# Connectors.net
KiCad netlist of a schematic drawn in Altium Designer
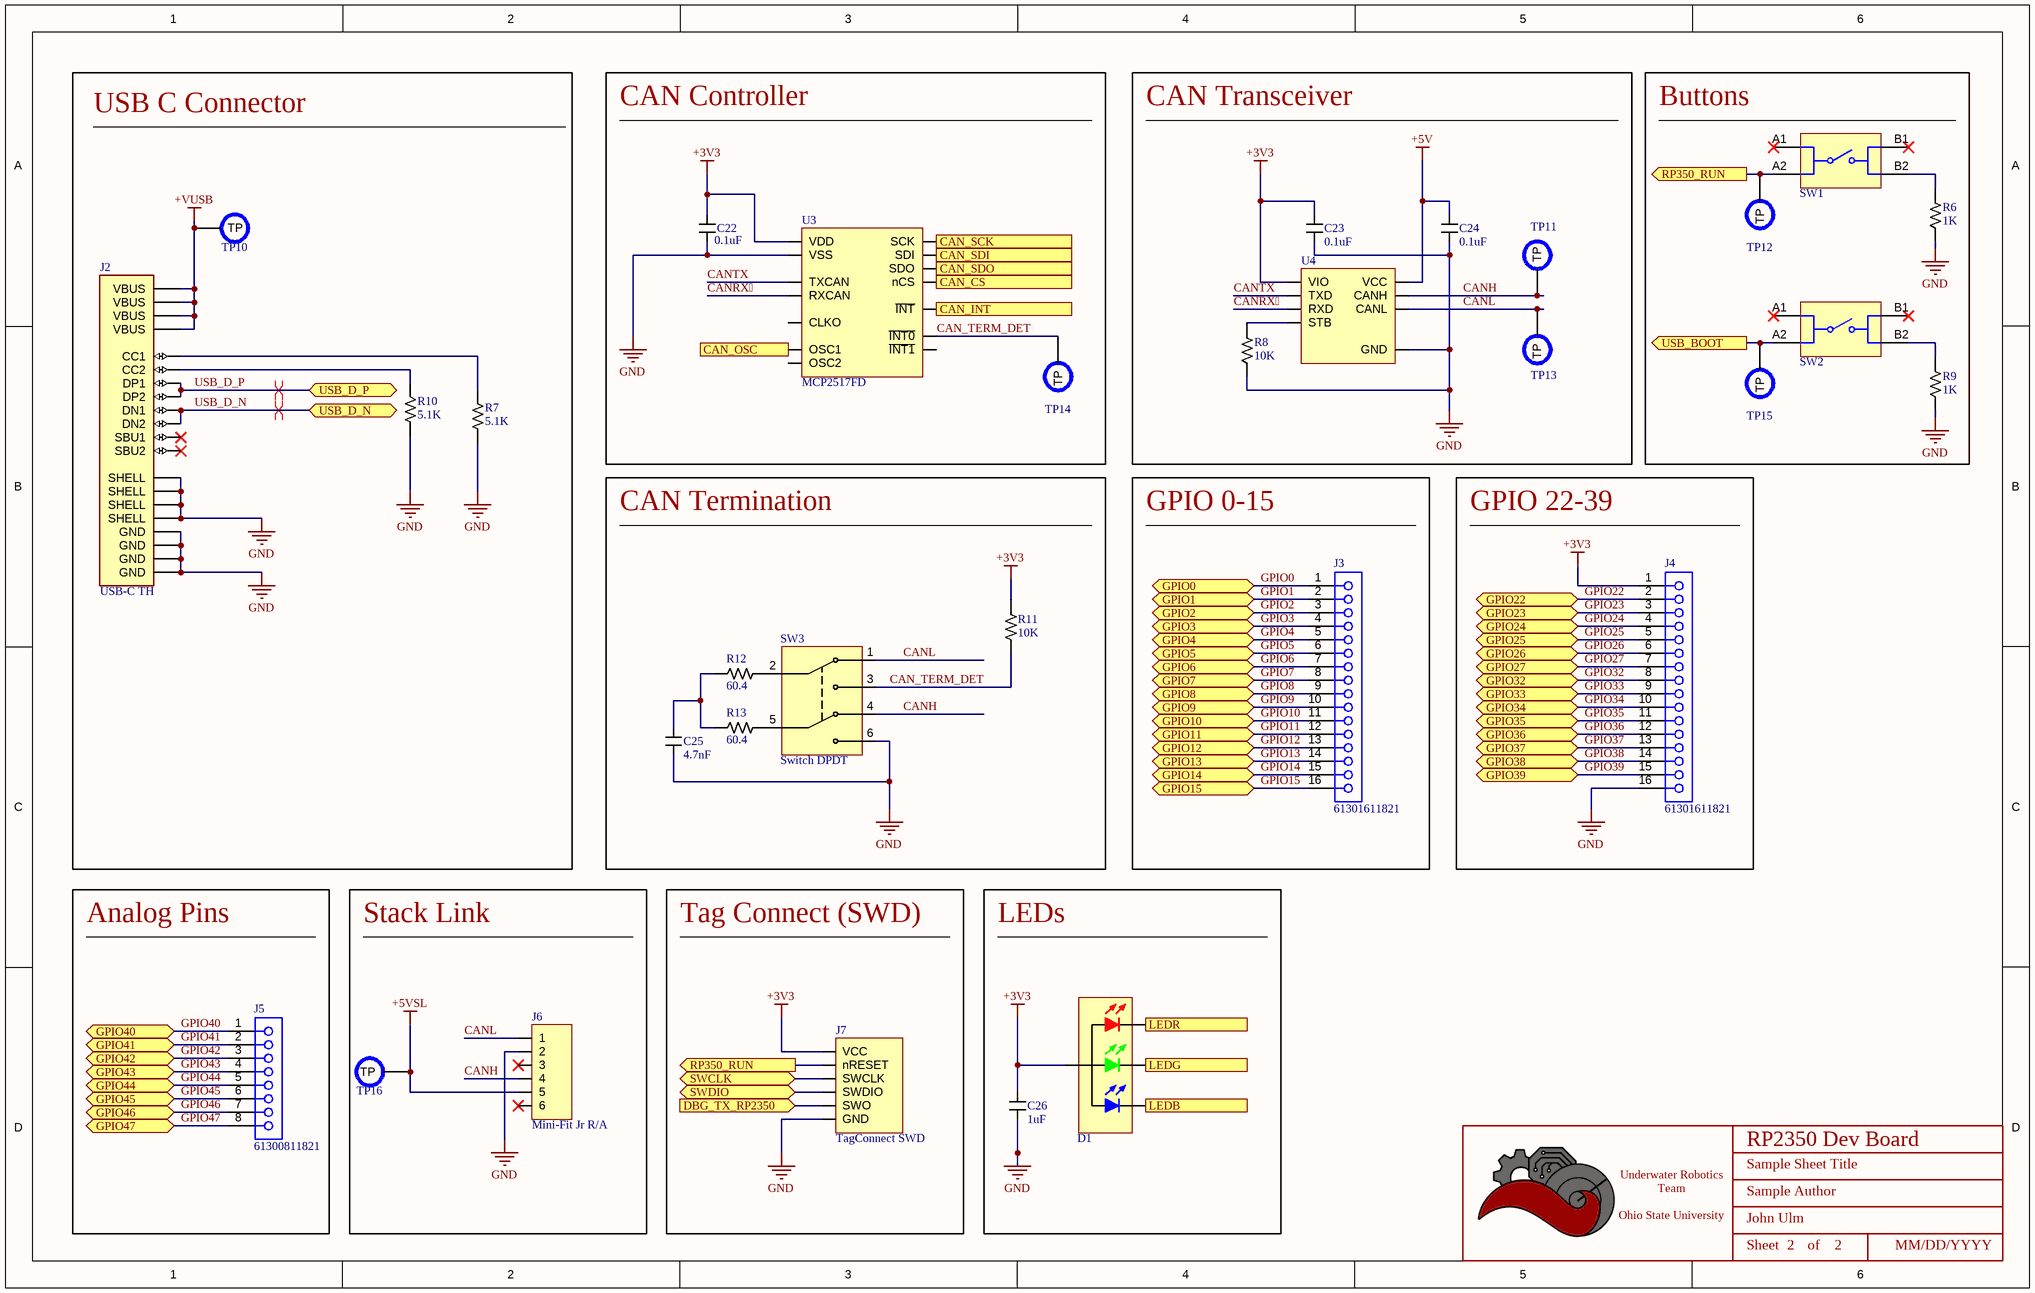
[diagram p0: Connectors.SchDoc]

(export (version "E")
  (design (tool "Eeschema 10.0.6"))
  (components
    (comp (ref "C22")
      (value "0.1uF")
      (footprint "CAPACITOR_0603")
      (description "Cap 100nF 25V +/-10%\r\nCeramic 0603")
      (fields
        (field (name "TOLERANCE") "+/- 10%")
        (field (name "VOLTAGE") "6.3V")
        (field (name "MADE BY") "Flip B")
      )
      (libsource (lib "Capacitors") (part "CAPACITOR_0.1uF_0603_25V"))
    )
    (comp (ref "C23")
      (value "0.1uF")
      (footprint "CAPACITOR_0603")
      (description "Cap 100nF 25V +/-10%\r\nCeramic 0603")
      (fields
        (field (name "TOLERANCE") "+/- 10%")
        (field (name "VOLTAGE") "6.3V")
        (field (name "MADE BY") "Flip B")
      )
      (libsource (lib "Capacitors") (part "CAPACITOR_0.1uF_0603_25V"))
    )
    (comp (ref "C24")
      (value "0.1uF")
      (footprint "CAPACITOR_0603")
      (description "Cap 100nF 25V +/-10%\r\nCeramic 0603")
      (fields
        (field (name "TOLERANCE") "+/- 10%")
        (field (name "VOLTAGE") "6.3V")
        (field (name "MADE BY") "Flip B")
      )
      (libsource (lib "Capacitors") (part "CAPACITOR_0.1uF_0603_25V"))
    )
    (comp (ref "C25")
      (value "4.7nF")
      (footprint "CAPACITOR_0402")
      (description "4700 pF +/-10% 25V Ceramic Capacitor X7R 0402")
      (fields
        (field (name "TOLERANCE") "+/- 10%")
        (field (name "VOLTAGE") "25V")
        (field (name "MADE BY") "Robert Pafford")
      )
      (libsource (lib "Capacitors") (part "CAPACITOR_0.0047uF_0402"))
    )
    (comp (ref "C26")
      (value "1uF")
      (footprint "CAPACITOR_0603")
      (description "Cap 1uF 16V +/-10%\r\nCeramic 0603")
      (fields
        (field (name "TOLERANCE") "+/- 10%")
        (field (name "VOLTAGE") "16V")
        (field (name "MADE BY") "Flip B")
      )
      (libsource (lib "Capacitors") (part "CAPACITOR_1uF_0603"))
    )
    (comp (ref "D1")
      (value "EAST1616RGBB4")
      (footprint "LED_0606_4SMD")
      (description "LED RGB CLEAR 4SMD")
      (fields (field (name "MADE BY") "Robert Pafford"))
      (libsource (lib "Diodes") (part "LED_RGB_4SMD"))
    )
    (comp (ref "J2")
      (value "USB-C TH")
      (footprint "USB-C TH")
      (description "USB-C (USB TYPE-C) USB 2.0 Receptacle Connector 24 (16+8 Dummy) Position Through Hole, Right Angle")
      (fields (field (name "CREATED BY") "John Ulm"))
      (libsource (lib "Connectors") (part "CONN_USBC_USB4085-GF-A"))
    )
    (comp (ref "J3")
      (value "61301611821")
      (footprint "61301611821")
      (libsource (lib "Altium Content Vault") (part "Header_Female_1R_16P"))
    )
    (comp (ref "J4")
      (value "61301611821")
      (footprint "61301611821")
      (libsource (lib "Altium Content Vault") (part "Header_Female_1R_16P"))
    )
    (comp (ref "J5")
      (value "61300811821")
      (footprint "61300811821")
      (libsource (lib "Altium Content Vault") (part "Header_Female_1R_08P"))
    )
    (comp (ref "J6")
      (value "Mini-Fit Jr R/A")
      (footprint "CONN_MOLEX_MINIFIT JR_6 POS_R/A")
      (description "Molex Minifit Jr. 5569 \r\n6 Pos R/A Natural")
      (fields (field (name "MANUFACTURER") "Molex") (field (name "CREATED BY") "Flip B"))
      (libsource (lib "Connectors") (part "CONN_MOLEX_MINIFIT JR_6POS_R/A"))
    )
    (comp (ref "J7")
      (value "TagConnect SWD")
      (footprint "TC2030-MCP")
      (description "TagConnect TC2030 ARM SWD 6-pin")
      (libsource (lib "Connectors") (part "TC2030_SWD"))
    )
    (comp (ref "R6")
      (value "1k Ohm 5% 1/8W")
      (footprint "RESISTOR_0603")
      (description "RES 1k OHM 5% 1/8W 0603")
      (fields
        (field (name "TOLERANCE") "+/- 5%")
        (field (name "VALUE  (OHMS)") "1K")
        (field (name "MADE BY") "Robert Pafford")
      )
      (libsource (lib "Resistors") (part "RESISTOR_1K_0603"))
    )
    (comp (ref "R7")
      (value "5.1k Ohm 1% 1/8W")
      (footprint "RESISTOR_0805")
      (description "RES 5.1k OHM 1% 1/8W 0805")
      (fields
        (field (name "TOLERANCE") "+/- 5%")
        (field (name "VALUE  (OHMS)") "5.1K")
        (field (name "MADE BY") "Dylan Trainor")
      )
      (libsource (lib "Resistors") (part "RESISTOR_5.1K_0805"))
    )
    (comp (ref "R8")
      (value "10k Ohm 1% 1/16W")
      (footprint "RESISTOR_0402")
      (description "RES 10k OHM 1% 1/16W 0402")
      (fields
        (field (name "TOLERANCE") "+/- 1%")
        (field (name "VALUE  (OHMS)") "10K")
        (field (name "MADE BY") "Robert Pafford")
      )
      (libsource (lib "Resistors") (part "RESISTOR_10K_0402"))
    )
    (comp (ref "R9")
      (value "1k Ohm 5% 1/8W")
      (footprint "RESISTOR_0603")
      (description "RES 1k OHM 5% 1/8W 0603")
      (fields
        (field (name "TOLERANCE") "+/- 5%")
        (field (name "VALUE  (OHMS)") "1K")
        (field (name "MADE BY") "Robert Pafford")
      )
      (libsource (lib "Resistors") (part "RESISTOR_1K_0603"))
    )
    (comp (ref "R10")
      (value "5.1k Ohm 1% 1/8W")
      (footprint "RESISTOR_0805")
      (description "RES 5.1k OHM 1% 1/8W 0805")
      (fields
        (field (name "TOLERANCE") "+/- 5%")
        (field (name "VALUE  (OHMS)") "5.1K")
        (field (name "MADE BY") "Dylan Trainor")
      )
      (libsource (lib "Resistors") (part "RESISTOR_5.1K_0805"))
    )
    (comp (ref "R11")
      (value "10k Ohm 1% 1/16W")
      (footprint "RESISTOR_0402")
      (description "RES 10k OHM 1% 1/16W 0402")
      (fields
        (field (name "TOLERANCE") "+/- 1%")
        (field (name "VALUE  (OHMS)") "10K")
        (field (name "MADE BY") "Robert Pafford")
      )
      (libsource (lib "Resistors") (part "RESISTOR_10K_0402"))
    )
    (comp (ref "R12")
      (value "60.4 Ohm 1% 1/16W")
      (footprint "RESISTOR_0402")
      (description "RES 60.4 OHM 1% 1/16W 0402")
      (fields
        (field (name "TOLERANCE") "+/- 1%")
        (field (name "VALUE  (OHMS)") "60.4")
        (field (name "MADE BY") "Robert Pafford")
      )
      (libsource (lib "Resistors") (part "RESISTOR_60.4_0402"))
    )
    (comp (ref "R13")
      (value "60.4 Ohm 1% 1/16W")
      (footprint "RESISTOR_0402")
      (description "RES 60.4 OHM 1% 1/16W 0402")
      (fields
        (field (name "TOLERANCE") "+/- 1%")
        (field (name "VALUE  (OHMS)") "60.4")
        (field (name "MADE BY") "Robert Pafford")
      )
      (libsource (lib "Resistors") (part "RESISTOR_60.4_0402"))
    )
    (comp (ref "SW1")
      (value "434123025826")
      (footprint "SMD_434123025826")
      (description "WS-TASV J-Bend SMT Tact Switch, SPST-NO, 16VDC, 50mA, 260g")
      (fields (field (name "MANUFACTURER") "Wurth Elektronik"))
      (libsource (lib "Switches") (part "Tactile Switch SMD"))
    )
    (comp (ref "SW2")
      (value "434123025826")
      (footprint "SMD_434123025826")
      (description "WS-TASV J-Bend SMT Tact Switch, SPST-NO, 16VDC, 50mA, 260g")
      (fields (field (name "MANUFACTURER") "Wurth Elektronik"))
      (libsource (lib "Switches") (part "Tactile Switch SMD"))
    )
    (comp (ref "SW3")
      (value "Switch DPDT")
      (footprint "CAS-220TA")
      (description "GOLD SWITCH FLUSH SLIDE DPDT 100MA 6V")
      (fields (field (name "MADE BY") "Robert Pafford"))
      (libsource (lib "Switches") (part "CAS-220TA_CAN_TERM"))
    )
    (comp (ref "TP10")
      (value "PCB Test Point")
      (footprint "TESTPOINT_1.2MM")
      (fields (field (name "MADE BY") "Robert Pafford"))
      (libsource (lib "Connectors") (part "TESTPOINT"))
    )
    (comp (ref "TP11")
      (value "PCB Test Point")
      (footprint "TESTPOINT_1.2MM")
      (fields (field (name "MADE BY") "Robert Pafford"))
      (libsource (lib "Connectors") (part "TESTPOINT"))
    )
    (comp (ref "TP12")
      (value "PCB Test Point")
      (footprint "TESTPOINT_1.2MM")
      (fields (field (name "MADE BY") "Robert Pafford"))
      (libsource (lib "Connectors") (part "TESTPOINT"))
    )
    (comp (ref "TP13")
      (value "PCB Test Point")
      (footprint "TESTPOINT_1.2MM")
      (fields (field (name "MADE BY") "Robert Pafford"))
      (libsource (lib "Connectors") (part "TESTPOINT"))
    )
    (comp (ref "TP14")
      (value "PCB Test Point")
      (footprint "TESTPOINT_1.2MM")
      (fields (field (name "MADE BY") "Robert Pafford"))
      (libsource (lib "Connectors") (part "TESTPOINT"))
    )
    (comp (ref "TP15")
      (value "PCB Test Point")
      (footprint "TESTPOINT_1.2MM")
      (fields (field (name "MADE BY") "Robert Pafford"))
      (libsource (lib "Connectors") (part "TESTPOINT"))
    )
    (comp (ref "TP16")
      (value "PCB Test Point")
      (footprint "TESTPOINT_1.2MM")
      (fields (field (name "MADE BY") "Robert Pafford"))
      (libsource (lib "Connectors") (part "TESTPOINT"))
    )
    (comp (ref "U3")
      (value "MCP2517FD")
      (footprint "SOIC-14")
      (description "CANbus Controller CAN 2.0 SPI Interface 14-SOIC")
      (fields (field (name "MADE BY") "Robert Pafford"))
      (libsource (lib "Integrated Circuits") (part "MCP2517FD"))
    )
    (comp (ref "U4")
      (value "CAN Transceiver")
      (footprint "SOIC-8")
      (description "CAN Interface IC High-Speed CAN Transceiver with Standby Mode")
      (fields (field (name "MADE BY") "Robert Pafford"))
      (libsource (lib "Integrated Circuits") (part "TJA1442AT"))
    )
  )
  (nets
    (net (code "1") (name "+3V3") (class "Default")
      (node (ref "C22") (pin "1") (pinfunction "1_1") (pintype "passive"))
      (node (ref "C23") (pin "1") (pinfunction "1_1") (pintype "passive"))
      (node (ref "C26") (pin "1") (pinfunction "1_1") (pintype "passive"))
      (node (ref "D1") (pin "4") (pinfunction "4_4") (pintype "passive"))
      (node (ref "J4") (pin "1") (pinfunction "1_1") (pintype "passive"))
      (node (ref "J7") (pin "2") (pinfunction "VCC_2") (pintype "passive"))
      (node (ref "R11") (pin "1") (pinfunction "1_1") (pintype "passive"))
      (node (ref "U3") (pin "14") (pinfunction "VDD_14") (pintype "passive"))
      (node (ref "U4") (pin "5") (pinfunction "VIO_5") (pintype "passive"))
    )
    (net (code "2") (name "+5V") (class "Default")
      (node (ref "C24") (pin "1") (pinfunction "1_1") (pintype "passive"))
      (node (ref "U4") (pin "3") (pinfunction "VCC_3") (pintype "passive"))
    )
    (net (code "3") (name "+5VSL") (class "Default")
      (node (ref "J6") (pin "5") (pinfunction "5_5") (pintype "passive"))
      (node (ref "TP16") (pin "TP") (pinfunction "TP_TP") (pintype "passive"))
    )
    (net (code "4") (name "+VUSB") (class "Default")
      (node (ref "J2") (pin "A4") (pinfunction "VBUS_A4") (pintype "power_in"))
      (node (ref "J2") (pin "A9") (pinfunction "VBUS_A9") (pintype "power_in"))
      (node (ref "J2") (pin "B4") (pinfunction "VBUS_B4") (pintype "power_in"))
      (node (ref "J2") (pin "B9") (pinfunction "VBUS_B9") (pintype "power_in"))
      (node (ref "TP10") (pin "TP") (pinfunction "TP_TP") (pintype "passive"))
    )
    (net (code "5") (name "/CANH") (class "Default")
      (node (ref "J6") (pin "4") (pinfunction "4_4") (pintype "passive"))
      (node (ref "SW3") (pin "4") (pintype "passive"))
      (node (ref "TP11") (pin "TP") (pinfunction "TP_TP") (pintype "passive"))
      (node (ref "U4") (pin "7") (pinfunction "CANH_7") (pintype "passive"))
    )
    (net (code "6") (name "/CANL") (class "Default")
      (node (ref "J6") (pin "1") (pinfunction "1_1") (pintype "passive"))
      (node (ref "SW3") (pin "1") (pintype "passive"))
      (node (ref "TP13") (pin "TP") (pinfunction "TP_TP") (pintype "passive"))
      (node (ref "U4") (pin "6") (pinfunction "CANL_6") (pintype "passive"))
    )
    (net (code "7") (name "/CANRX") (class "Default")
      (node (ref "U3") (pin "2") (pinfunction "RXCAN_2") (pintype "passive"))
      (node (ref "U4") (pin "4") (pinfunction "RXD_4") (pintype "passive"))
    )
    (net (code "8") (name "/CANTX") (class "Default")
      (node (ref "U3") (pin "1") (pinfunction "TXCAN_1") (pintype "passive"))
      (node (ref "U4") (pin "1") (pinfunction "TXD_1") (pintype "passive"))
    )
    (net (code "9") (name "/CAN_CS") (class "Default")
      (node (ref "U3") (pin "13") (pinfunction "nCS_13") (pintype "passive"))
    )
    (net (code "10") (name "/CAN_INT") (class "Default")
      (node (ref "U3") (pin "4") (pinfunction "~{INT}_4") (pintype "passive"))
    )
    (net (code "11") (name "/CAN_OSC") (class "Default")
      (node (ref "U3") (pin "6") (pinfunction "OSC1_6") (pintype "passive"))
    )
    (net (code "12") (name "/CAN_SCK") (class "Default")
      (node (ref "U3") (pin "10") (pinfunction "SCK_10") (pintype "passive"))
    )
    (net (code "13") (name "/CAN_SDI") (class "Default")
      (node (ref "U3") (pin "11") (pinfunction "SDI_11") (pintype "passive"))
    )
    (net (code "14") (name "/CAN_SDO") (class "Default")
      (node (ref "U3") (pin "12") (pinfunction "SDO_12") (pintype "passive"))
    )
    (net (code "15") (name "/CAN_TERM_DET") (class "Default")
      (node (ref "R11") (pin "2") (pinfunction "2_2") (pintype "passive"))
      (node (ref "SW3") (pin "3") (pintype "passive"))
      (node (ref "TP14") (pin "TP") (pinfunction "TP_TP") (pintype "passive"))
      (node (ref "U3") (pin "9") (pinfunction "~{INT0}_9") (pintype "passive"))
    )
    (net (code "16") (name "/DBG_TX_RP2350") (class "Default")
      (node (ref "J7") (pin "5") (pinfunction "SWO_5") (pintype "passive"))
    )
    (net (code "17") (name "/GPIO0") (class "Default")
      (node (ref "J3") (pin "1") (pinfunction "1_1") (pintype "passive"))
    )
    (net (code "18") (name "/GPIO1") (class "Default")
      (node (ref "J3") (pin "2") (pinfunction "2_2") (pintype "passive"))
    )
    (net (code "19") (name "/GPIO2") (class "Default")
      (node (ref "J3") (pin "3") (pinfunction "3_3") (pintype "passive"))
    )
    (net (code "20") (name "/GPIO3") (class "Default")
      (node (ref "J3") (pin "4") (pinfunction "4_4") (pintype "passive"))
    )
    (net (code "21") (name "/GPIO4") (class "Default")
      (node (ref "J3") (pin "5") (pinfunction "5_5") (pintype "passive"))
    )
    (net (code "22") (name "/GPIO5") (class "Default")
      (node (ref "J3") (pin "6") (pinfunction "6_6") (pintype "passive"))
    )
    (net (code "23") (name "/GPIO6") (class "Default")
      (node (ref "J3") (pin "7") (pinfunction "7_7") (pintype "passive"))
    )
    (net (code "24") (name "/GPIO7") (class "Default")
      (node (ref "J3") (pin "8") (pinfunction "8_8") (pintype "passive"))
    )
    (net (code "25") (name "/GPIO8") (class "Default")
      (node (ref "J3") (pin "9") (pinfunction "9_9") (pintype "passive"))
    )
    (net (code "26") (name "/GPIO9") (class "Default")
      (node (ref "J3") (pin "10") (pinfunction "10_10") (pintype "passive"))
    )
    (net (code "27") (name "/GPIO10") (class "Default")
      (node (ref "J3") (pin "11") (pinfunction "11_11") (pintype "passive"))
    )
    (net (code "28") (name "/GPIO11") (class "Default")
      (node (ref "J3") (pin "12") (pinfunction "12_12") (pintype "passive"))
    )
    (net (code "29") (name "/GPIO12") (class "Default")
      (node (ref "J3") (pin "13") (pinfunction "13_13") (pintype "passive"))
    )
    (net (code "30") (name "/GPIO13") (class "Default")
      (node (ref "J3") (pin "14") (pinfunction "14_14") (pintype "passive"))
    )
    (net (code "31") (name "/GPIO14") (class "Default")
      (node (ref "J3") (pin "15") (pinfunction "15_15") (pintype "passive"))
    )
    (net (code "32") (name "/GPIO15") (class "Default")
      (node (ref "J3") (pin "16") (pinfunction "16_16") (pintype "passive"))
    )
    (net (code "33") (name "/GPIO22") (class "Default")
      (node (ref "J4") (pin "2") (pinfunction "2_2") (pintype "passive"))
    )
    (net (code "34") (name "/GPIO23") (class "Default")
      (node (ref "J4") (pin "3") (pinfunction "3_3") (pintype "passive"))
    )
    (net (code "35") (name "/GPIO24") (class "Default")
      (node (ref "J4") (pin "4") (pinfunction "4_4") (pintype "passive"))
    )
    (net (code "36") (name "/GPIO25") (class "Default")
      (node (ref "J4") (pin "5") (pinfunction "5_5") (pintype "passive"))
    )
    (net (code "37") (name "/GPIO26") (class "Default")
      (node (ref "J4") (pin "6") (pinfunction "6_6") (pintype "passive"))
    )
    (net (code "38") (name "/GPIO27") (class "Default")
      (node (ref "J4") (pin "7") (pinfunction "7_7") (pintype "passive"))
    )
    (net (code "39") (name "/GPIO32") (class "Default")
      (node (ref "J4") (pin "8") (pinfunction "8_8") (pintype "passive"))
    )
    (net (code "40") (name "/GPIO33") (class "Default")
      (node (ref "J4") (pin "9") (pinfunction "9_9") (pintype "passive"))
    )
    (net (code "41") (name "/GPIO34") (class "Default")
      (node (ref "J4") (pin "10") (pinfunction "10_10") (pintype "passive"))
    )
    (net (code "42") (name "/GPIO35") (class "Default")
      (node (ref "J4") (pin "11") (pinfunction "11_11") (pintype "passive"))
    )
    (net (code "43") (name "/GPIO36") (class "Default")
      (node (ref "J4") (pin "12") (pinfunction "12_12") (pintype "passive"))
    )
    (net (code "44") (name "/GPIO37") (class "Default")
      (node (ref "J4") (pin "13") (pinfunction "13_13") (pintype "passive"))
    )
    (net (code "45") (name "/GPIO38") (class "Default")
      (node (ref "J4") (pin "14") (pinfunction "14_14") (pintype "passive"))
    )
    (net (code "46") (name "/GPIO39") (class "Default")
      (node (ref "J4") (pin "15") (pinfunction "15_15") (pintype "passive"))
    )
    (net (code "47") (name "/GPIO40") (class "Default")
      (node (ref "J5") (pin "1") (pinfunction "1_1") (pintype "passive"))
    )
    (net (code "48") (name "/GPIO41") (class "Default")
      (node (ref "J5") (pin "2") (pinfunction "2_2") (pintype "passive"))
    )
    (net (code "49") (name "/GPIO42") (class "Default")
      (node (ref "J5") (pin "3") (pinfunction "3_3") (pintype "passive"))
    )
    (net (code "50") (name "/GPIO43") (class "Default")
      (node (ref "J5") (pin "4") (pinfunction "4_4") (pintype "passive"))
    )
    (net (code "51") (name "/GPIO44") (class "Default")
      (node (ref "J5") (pin "5") (pinfunction "5_5") (pintype "passive"))
    )
    (net (code "52") (name "/GPIO45") (class "Default")
      (node (ref "J5") (pin "6") (pinfunction "6_6") (pintype "passive"))
    )
    (net (code "53") (name "/GPIO46") (class "Default")
      (node (ref "J5") (pin "7") (pinfunction "7_7") (pintype "passive"))
    )
    (net (code "54") (name "/GPIO47") (class "Default")
      (node (ref "J5") (pin "8") (pinfunction "8_8") (pintype "passive"))
    )
    (net (code "55") (name "/LEDB") (class "Default")
      (node (ref "D1") (pin "3") (pinfunction "32_3") (pintype "passive"))
    )
    (net (code "56") (name "/LEDG") (class "Default")
      (node (ref "D1") (pin "2") (pinfunction "2_2") (pintype "passive"))
    )
    (net (code "57") (name "/LEDR") (class "Default")
      (node (ref "D1") (pin "1") (pinfunction "1_1") (pintype "passive"))
    )
    (net (code "58") (name "/RP350_RUN") (class "Default")
      (node (ref "J7") (pin "4") (pinfunction "nRESET_4") (pintype "passive"))
      (node (ref "SW1") (pin "A2") (pinfunction "A2_A2") (pintype "passive"))
      (node (ref "TP12") (pin "TP") (pinfunction "TP_TP") (pintype "passive"))
    )
    (net (code "59") (name "/SWCLK") (class "Default")
      (node (ref "J7") (pin "3") (pinfunction "SWCLK_3") (pintype "passive"))
    )
    (net (code "60") (name "/SWDIO") (class "Default")
      (node (ref "J7") (pin "1") (pinfunction "SWDIO_1") (pintype "passive"))
    )
    (net (code "61") (name "/USB_BOOT") (class "Default")
      (node (ref "SW2") (pin "A2") (pinfunction "A2_A2") (pintype "passive"))
      (node (ref "TP15") (pin "TP") (pinfunction "TP_TP") (pintype "passive"))
    )
    (net (code "62") (name "/USB_D_N") (class "Default")
      (node (ref "J2") (pin "A7") (pinfunction "DN1_A7") (pintype "bidirectional"))
      (node (ref "J2") (pin "B7") (pinfunction "DN2_B7") (pintype "bidirectional"))
    )
    (net (code "63") (name "/USB_D_P") (class "Default")
      (node (ref "J2") (pin "A6") (pinfunction "DP1_A6") (pintype "bidirectional"))
      (node (ref "J2") (pin "B6") (pinfunction "DP2_B6") (pintype "bidirectional"))
    )
    (net (code "64") (name "GND") (class "Default")
      (node (ref "C22") (pin "2") (pinfunction "2_2") (pintype "passive"))
      (node (ref "C23") (pin "2") (pinfunction "2_2") (pintype "passive"))
      (node (ref "C24") (pin "2") (pinfunction "2_2") (pintype "passive"))
      (node (ref "C25") (pin "2") (pinfunction "2_2") (pintype "passive"))
      (node (ref "C26") (pin "2") (pinfunction "2_2") (pintype "passive"))
      (node (ref "J2") (pin "A1") (pinfunction "GND_A1") (pintype "power_in"))
      (node (ref "J2") (pin "A12") (pinfunction "GND_A12") (pintype "power_in"))
      (node (ref "J2") (pin "B1") (pinfunction "GND_B1") (pintype "power_in"))
      (node (ref "J2") (pin "B12") (pinfunction "GND_B12") (pintype "power_in"))
      (node (ref "J2") (pin "S1") (pinfunction "SHELL_S1") (pintype "passive"))
      (node (ref "J2") (pin "S2") (pinfunction "SHELL_S2") (pintype "passive"))
      (node (ref "J2") (pin "S3") (pinfunction "SHELL_S3") (pintype "passive"))
      (node (ref "J2") (pin "S4") (pinfunction "SHELL_S4") (pintype "passive"))
      (node (ref "J4") (pin "16") (pinfunction "16_16") (pintype "passive"))
      (node (ref "J6") (pin "2") (pinfunction "2_2") (pintype "passive"))
      (node (ref "J7") (pin "6") (pinfunction "GND_6") (pintype "passive"))
      (node (ref "R10") (pin "1") (pinfunction "1_1") (pintype "passive"))
      (node (ref "R6") (pin "2") (pinfunction "2_2") (pintype "passive"))
      (node (ref "R7") (pin "1") (pinfunction "1_1") (pintype "passive"))
      (node (ref "R8") (pin "2") (pinfunction "2_2") (pintype "passive"))
      (node (ref "R9") (pin "2") (pinfunction "2_2") (pintype "passive"))
      (node (ref "SW3") (pin "6") (pintype "passive"))
      (node (ref "U3") (pin "7") (pinfunction "VSS_7") (pintype "passive"))
      (node (ref "U4") (pin "2") (pinfunction "GND_2") (pintype "passive"))
    )
    (net (code "65") (name "Net-(C25-Pad1)") (class "Default")
      (node (ref "C25") (pin "1") (pinfunction "1_1") (pintype "passive"))
      (node (ref "R12") (pin "2") (pinfunction "2_2") (pintype "passive"))
      (node (ref "R13") (pin "2") (pinfunction "2_2") (pintype "passive"))
    )
    (net (code "66") (name "Net-(J2-CC1)") (class "Default")
      (node (ref "J2") (pin "A5") (pinfunction "CC1_A5") (pintype "bidirectional"))
      (node (ref "R7") (pin "2") (pinfunction "2_2") (pintype "passive"))
    )
    (net (code "67") (name "Net-(J2-CC2)") (class "Default")
      (node (ref "J2") (pin "B5") (pinfunction "CC2_B5") (pintype "bidirectional"))
      (node (ref "R10") (pin "2") (pinfunction "2_2") (pintype "passive"))
    )
    (net (code "68") (name "Net-(R6-Pad1)") (class "Default")
      (node (ref "R6") (pin "1") (pinfunction "1_1") (pintype "passive"))
      (node (ref "SW1") (pin "B2") (pinfunction "B2_B2") (pintype "passive"))
    )
    (net (code "69") (name "Net-(R9-Pad1)") (class "Default")
      (node (ref "R9") (pin "1") (pinfunction "1_1") (pintype "passive"))
      (node (ref "SW2") (pin "B2") (pinfunction "B2_B2") (pintype "passive"))
    )
    (net (code "70") (name "Net-(R12-Pad1)") (class "Default")
      (node (ref "R12") (pin "1") (pinfunction "1_1") (pintype "passive"))
      (node (ref "SW3") (pin "2") (pintype "passive"))
    )
    (net (code "71") (name "Net-(R13-Pad1)") (class "Default")
      (node (ref "R13") (pin "1") (pinfunction "1_1") (pintype "passive"))
      (node (ref "SW3") (pin "5") (pintype "passive"))
    )
    (net (code "72") (name "Net-(U4-STB)") (class "Default")
      (node (ref "R8") (pin "1") (pinfunction "1_1") (pintype "passive"))
      (node (ref "U4") (pin "8") (pinfunction "STB_8") (pintype "passive"))
    )
    (net (code "73") (name "unconnected-(J2-SBU1-PadA8)") (class "Default")
      (node (ref "J2") (pin "A8") (pinfunction "SBU1_A8") (pintype "bidirectional+no_connect"))
    )
    (net (code "74") (name "unconnected-(J2-SBU2-PadB8)") (class "Default")
      (node (ref "J2") (pin "B8") (pinfunction "SBU2_B8") (pintype "bidirectional+no_connect"))
    )
    (net (code "75") (name "unconnected-(J6-Pad3)") (class "Default")
      (node (ref "J6") (pin "3") (pinfunction "3_3") (pintype "passive+no_connect"))
    )
    (net (code "76") (name "unconnected-(J6-Pad6)") (class "Default")
      (node (ref "J6") (pin "6") (pinfunction "6_6") (pintype "passive+no_connect"))
    )
    (net (code "77") (name "unconnected-(SW1-PadA1)") (class "Default")
      (node (ref "SW1") (pin "A1") (pinfunction "A1_A1") (pintype "passive+no_connect"))
    )
    (net (code "78") (name "unconnected-(SW1-PadB1)") (class "Default")
      (node (ref "SW1") (pin "B1") (pinfunction "B1_B1") (pintype "passive+no_connect"))
    )
    (net (code "79") (name "unconnected-(SW2-PadA1)") (class "Default")
      (node (ref "SW2") (pin "A1") (pinfunction "A1_A1") (pintype "passive+no_connect"))
    )
    (net (code "80") (name "unconnected-(SW2-PadB1)") (class "Default")
      (node (ref "SW2") (pin "B1") (pinfunction "B1_B1") (pintype "passive+no_connect"))
    )
    (net (code "81") (name "unconnected-(U3-CLKO-Pad3)") (class "Default")
      (node (ref "U3") (pin "3") (pinfunction "CLKO_3") (pintype "passive"))
    )
    (net (code "82") (name "unconnected-(U3-OSC2-Pad5)") (class "Default")
      (node (ref "U3") (pin "5") (pinfunction "OSC2_5") (pintype "passive"))
    )
    (net (code "83") (name "unconnected-(U3-~{INT1}-Pad8)") (class "Default")
      (node (ref "U3") (pin "8") (pinfunction "~{INT1}_8") (pintype "passive"))
    )
  )
)
